# Microcontroller_Schematic.net
KiCad netlist of a schematic drawn in Altium Designer
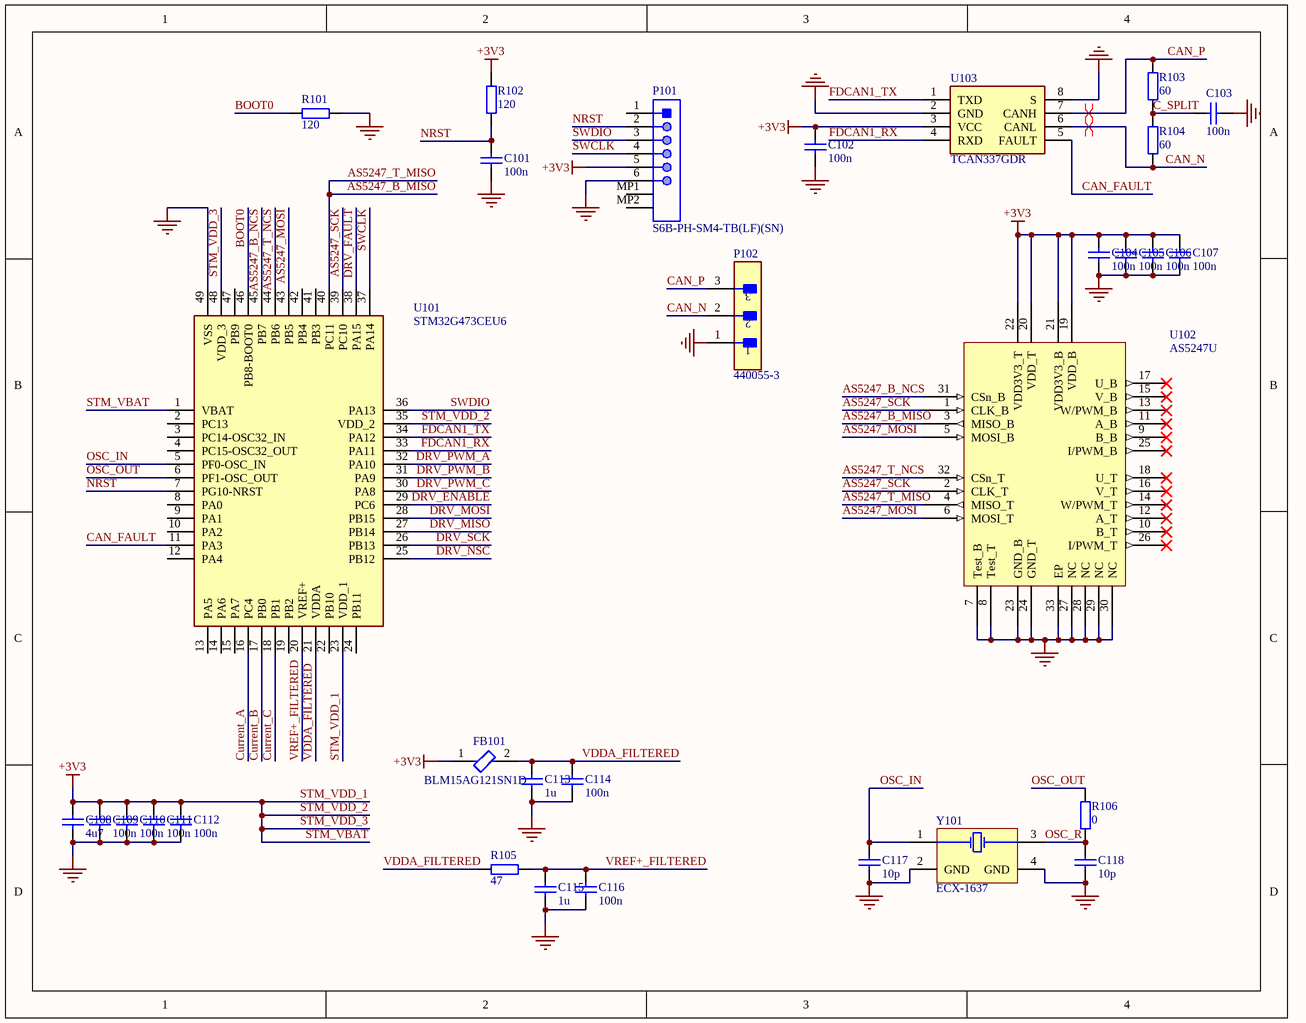
[diagram p0: Microcontroller Schematic.SchDoc]

(export (version "E")
  (design (tool "Eeschema 10.0.6"))
  (components
    (comp (ref "C101")
      (value "100n")
      (footprint "FootprintLib:CAPC1005X55N")
      (description "Capacitor")
      (fields
        (field (name "MANUFACTURER_PART_NUMBER") "CL05B104KO5NNNC")
        (field (name "MOUSER PART NUMBER") "187-CL05B104KO5NNNC")
      )
      (libsource (lib "SymbolLib") (part "CAP_0402_16V"))
    )
    (comp (ref "C102")
      (value "100n")
      (footprint "FootprintLib:CAPC1005X55N")
      (description "Capacitor")
      (fields
        (field (name "MANUFACTURER_PART_NUMBER") "CL05B104KO5NNNC")
        (field (name "MOUSER PART NUMBER") "187-CL05B104KO5NNNC")
      )
      (libsource (lib "SymbolLib") (part "CAP_0402_16V"))
    )
    (comp (ref "C103")
      (value "100n")
      (footprint "FootprintLib:CAPC1005X55N")
      (description "Capacitor")
      (fields
        (field (name "MANUFACTURER_PART_NUMBER") "CL05B104KO5NNNC")
        (field (name "MOUSER PART NUMBER") "187-CL05B104KO5NNNC")
      )
      (libsource (lib "SymbolLib") (part "CAP_0402_16V"))
    )
    (comp (ref "C104")
      (value "100n")
      (footprint "FootprintLib:CAPC1005X55N")
      (description "Capacitor")
      (fields
        (field (name "MANUFACTURER_PART_NUMBER") "CL05B104KO5NNNC")
        (field (name "MOUSER PART NUMBER") "187-CL05B104KO5NNNC")
      )
      (libsource (lib "SymbolLib") (part "CAP_0402_16V"))
    )
    (comp (ref "C105")
      (value "100n")
      (footprint "FootprintLib:CAPC1005X55N")
      (description "Capacitor")
      (fields
        (field (name "MANUFACTURER_PART_NUMBER") "CL05B104KO5NNNC")
        (field (name "MOUSER PART NUMBER") "187-CL05B104KO5NNNC")
      )
      (libsource (lib "SymbolLib") (part "CAP_0402_16V"))
    )
    (comp (ref "C106")
      (value "100n")
      (footprint "FootprintLib:CAPC1005X55N")
      (description "Capacitor")
      (fields
        (field (name "MANUFACTURER_PART_NUMBER") "CL05B104KO5NNNC")
        (field (name "MOUSER PART NUMBER") "187-CL05B104KO5NNNC")
      )
      (libsource (lib "SymbolLib") (part "CAP_0402_16V"))
    )
    (comp (ref "C107")
      (value "100n")
      (footprint "FootprintLib:CAPC1005X55N")
      (description "Capacitor")
      (fields
        (field (name "MANUFACTURER_PART_NUMBER") "CL05B104KO5NNNC")
        (field (name "MOUSER PART NUMBER") "187-CL05B104KO5NNNC")
      )
      (libsource (lib "SymbolLib") (part "CAP_0402_16V"))
    )
    (comp (ref "C108")
      (value "4u7")
      (footprint "FootprintLib:CAPC1608X90N")
      (description "Capacitor")
      (fields
        (field (name "MANUFACTURER_PART_NUMBER") "CL05B104KO5NNNC")
        (field (name "MOUSER PART NUMBER") "187-CL05B104KO5NNNC")
      )
      (libsource (lib "SymbolLib") (part "CAP_0603_16V"))
    )
    (comp (ref "C109")
      (value "100n")
      (footprint "FootprintLib:CAPC1005X55N")
      (description "Capacitor")
      (fields
        (field (name "MANUFACTURER_PART_NUMBER") "CL05B104KO5NNNC")
        (field (name "MOUSER PART NUMBER") "187-CL05B104KO5NNNC")
      )
      (libsource (lib "SymbolLib") (part "CAP_0402_16V"))
    )
    (comp (ref "C110")
      (value "100n")
      (footprint "FootprintLib:CAPC1005X55N")
      (description "Capacitor")
      (fields
        (field (name "MANUFACTURER_PART_NUMBER") "CL05B104KO5NNNC")
        (field (name "MOUSER PART NUMBER") "187-CL05B104KO5NNNC")
      )
      (libsource (lib "SymbolLib") (part "CAP_0402_16V"))
    )
    (comp (ref "C111")
      (value "100n")
      (footprint "FootprintLib:CAPC1005X55N")
      (description "Capacitor")
      (fields
        (field (name "MANUFACTURER_PART_NUMBER") "CL05B104KO5NNNC")
        (field (name "MOUSER PART NUMBER") "187-CL05B104KO5NNNC")
      )
      (libsource (lib "SymbolLib") (part "CAP_0402_16V"))
    )
    (comp (ref "C112")
      (value "100n")
      (footprint "FootprintLib:CAPC1005X55N")
      (description "Capacitor")
      (fields
        (field (name "MANUFACTURER_PART_NUMBER") "CL05B104KO5NNNC")
        (field (name "MOUSER PART NUMBER") "187-CL05B104KO5NNNC")
      )
      (libsource (lib "SymbolLib") (part "CAP_0402_16V"))
    )
    (comp (ref "C113")
      (value "1u")
      (footprint "FootprintLib:CAPC1005X55N")
      (description "Capacitor")
      (fields
        (field (name "MANUFACTURER_PART_NUMBER") "CL05B104KO5NNNC")
        (field (name "MOUSER PART NUMBER") "187-CL05B104KO5NNNC")
      )
      (libsource (lib "SymbolLib") (part "CAP_0402_16V"))
    )
    (comp (ref "C114")
      (value "100n")
      (footprint "FootprintLib:CAPC1005X55N")
      (description "Capacitor")
      (fields
        (field (name "MANUFACTURER_PART_NUMBER") "CL05B104KO5NNNC")
        (field (name "MOUSER PART NUMBER") "187-CL05B104KO5NNNC")
      )
      (libsource (lib "SymbolLib") (part "CAP_0402_16V"))
    )
    (comp (ref "C115")
      (value "1u")
      (footprint "FootprintLib:CAPC1005X55N")
      (description "Capacitor")
      (fields
        (field (name "MANUFACTURER_PART_NUMBER") "CL05B104KO5NNNC")
        (field (name "MOUSER PART NUMBER") "187-CL05B104KO5NNNC")
      )
      (libsource (lib "SymbolLib") (part "CAP_0402_16V"))
    )
    (comp (ref "C116")
      (value "100n")
      (footprint "FootprintLib:CAPC1005X55N")
      (description "Capacitor")
      (fields
        (field (name "MANUFACTURER_PART_NUMBER") "CL05B104KO5NNNC")
        (field (name "MOUSER PART NUMBER") "187-CL05B104KO5NNNC")
      )
      (libsource (lib "SymbolLib") (part "CAP_0402_16V"))
    )
    (comp (ref "C117")
      (value "10p")
      (footprint "FootprintLib:CAPC1005X55N")
      (description "Capacitor")
      (fields
        (field (name "MANUFACTURER_PART_NUMBER") "CL05B104KO5NNNC")
        (field (name "MOUSER PART NUMBER") "187-CL05B104KO5NNNC")
      )
      (libsource (lib "SymbolLib") (part "CAP_0402_16V"))
    )
    (comp (ref "C118")
      (value "10p")
      (footprint "FootprintLib:CAPC1005X55N")
      (description "Capacitor")
      (fields
        (field (name "MANUFACTURER_PART_NUMBER") "CL05B104KO5NNNC")
        (field (name "MOUSER PART NUMBER") "187-CL05B104KO5NNNC")
      )
      (libsource (lib "SymbolLib") (part "CAP_0402_16V"))
    )
    (comp (ref "FB101")
      (value "BLM15AG121SN1D")
      (footprint "FP-BLM15-0_05-MFG")
      (description "Chip Ferrite Bead, 0402, 120Ω @ 100MHz, 0.19Ω, 25%, 550mA")
      (fields (field (name "TOLERANCE") "25%"))
      (libsource (lib "Altium Content Vault") (part "5f30dd21d616792df468990f7003faa"))
    )
    (comp (ref "P101")
      (value "S6B-PH-SM4-TB(LF)(SN)")
      (footprint "JST-S6B-PH-SM4-TB(LF)(SN)_V")
      (description "Male Header, Pitch 2 mm, 1 x 6 Position, Height 5.5 mm, -25 to 85 degC")
      (fields (field (name "MANUFACTURER") "JST"))
      (libsource (lib "Altium Content Vault") (part "CN-1P-2M-R6"))
    )
    (comp (ref "P102")
      (value "440055-3")
      (footprint "FP-440055-3-MFG")
      (description "CONN HEADER R/A 3POS 2MM")
      (fields
        (field (name "MANUFACTURER") "TE Connectivity")
        (field (name "OCTOPART") "https://octopart.com/440055-3-te+connectivity-40644627")
      )
      (libsource (lib "Altium Content Vault") (part "0d3f023dd272f625e17a2be33dea85f"))
    )
    (comp (ref "R101")
      (value "120")
      (footprint "FootprintLib:RESC1005X40N")
      (libsource (lib "SymbolLib") (part "RES_0402"))
    )
    (comp (ref "R102")
      (value "120")
      (footprint "FootprintLib:RESC1005X40N")
      (libsource (lib "SymbolLib") (part "RES_0402"))
    )
    (comp (ref "R103")
      (value "60")
      (footprint "FootprintLib:RESC1005X40N")
      (libsource (lib "SymbolLib") (part "RES_0402"))
    )
    (comp (ref "R104")
      (value "60")
      (footprint "FootprintLib:RESC1005X40N")
      (libsource (lib "SymbolLib") (part "RES_0402"))
    )
    (comp (ref "R105")
      (value "47")
      (footprint "FootprintLib:RESC1005X40N")
      (libsource (lib "SymbolLib") (part "RES_0402"))
    )
    (comp (ref "R106")
      (value "0")
      (footprint "FootprintLib:RESC1005X40N")
      (libsource (lib "SymbolLib") (part "RES_0402"))
    )
    (comp (ref "U101")
      (value "STM32G473CEU6")
      (footprint "SamacSys:QFN50P700X700X65-49N-D")
      (description "Integrated Circuit")
      (fields (field (name "MOUSER PART NUMBER") "511-STM32G473CEU6"))
      (libsource (lib "*") (part "STM32G473CEU6"))
    )
    (comp (ref "U102")
      (value "AS5247U")
      (footprint "QFN-N32-THM")
      (description "ams AS5247U Magnetic Rotary Position Sensor")
      (libsource (lib "SymbolLib") (part "AS5247U"))
    )
    (comp (ref "U103")
      (value "TCAN337GDR")
      (footprint "SamacSys:SOIC127P600X175-8N")
      (description "Integrated Circuit")
      (fields (field (name "MOUSER PART NUMBER") "595-TCAN337GDR"))
      (libsource (lib "*") (part "TCAN337GDR"))
    )
    (comp (ref "Y101")
      (value "ECX-1637")
      (footprint "ECX-1637")
      (libsource (lib "SymbolLib") (part "ECX-1637"))
    )
  )
  (nets
    (net (code "1") (name "+3V3") (class "Default")
      (node (ref "C102") (pin "2") (pinfunction "2_2") (pintype "passive"))
      (node (ref "C104") (pin "2") (pinfunction "2_2") (pintype "passive"))
      (node (ref "C105") (pin "2") (pinfunction "2_2") (pintype "passive"))
      (node (ref "C106") (pin "2") (pinfunction "2_2") (pintype "passive"))
      (node (ref "C107") (pin "2") (pinfunction "2_2") (pintype "passive"))
      (node (ref "C108") (pin "1") (pinfunction "1_1") (pintype "passive"))
      (node (ref "C109") (pin "2") (pinfunction "2_2") (pintype "passive"))
      (node (ref "C110") (pin "2") (pinfunction "2_2") (pintype "passive"))
      (node (ref "C111") (pin "2") (pinfunction "2_2") (pintype "passive"))
      (node (ref "C112") (pin "2") (pinfunction "2_2") (pintype "passive"))
      (node (ref "FB101") (pin "1") (pinfunction "1_1") (pintype "passive"))
      (node (ref "P101") (pin "5") (pinfunction "5_5") (pintype "passive"))
      (node (ref "R102") (pin "1") (pinfunction "1_1") (pintype "passive"))
      (node (ref "U101") (pin "1") (pinfunction "VBAT_1") (pintype "passive"))
      (node (ref "U101") (pin "23") (pinfunction "VDD_1_23") (pintype "passive"))
      (node (ref "U101") (pin "35") (pinfunction "VDD_2_35") (pintype "passive"))
      (node (ref "U101") (pin "48") (pinfunction "VDD_3_48") (pintype "passive"))
      (node (ref "U102") (pin "19") (pinfunction "VDD_B_19") (pintype "power_in"))
      (node (ref "U102") (pin "20") (pinfunction "VDD_T_20") (pintype "power_in"))
      (node (ref "U102") (pin "21") (pinfunction "VDD3V3_B_21") (pintype "power_in"))
      (node (ref "U102") (pin "22") (pinfunction "VDD3V3_T_22") (pintype "power_in"))
      (node (ref "U103") (pin "3") (pinfunction "VCC_3") (pintype "passive"))
    )
    (net (code "2") (name "/AS5247_B_MISO") (class "Default")
      (node (ref "U101") (pin "40") (pinfunction "PC11_40") (pintype "passive"))
      (node (ref "U102") (pin "3") (pinfunction "MISO_B_3") (pintype "output"))
      (node (ref "U102") (pin "4") (pinfunction "MISO_T_4") (pintype "output"))
    )
    (net (code "3") (name "/AS5247_B_NCS") (class "Default")
      (node (ref "U101") (pin "45") (pinfunction "PB7_45") (pintype "passive"))
      (node (ref "U102") (pin "31") (pinfunction "CSn_B_31") (pintype "input"))
    )
    (net (code "4") (name "/AS5247_MOSI") (class "Default")
      (node (ref "U101") (pin "43") (pinfunction "PB5_43") (pintype "passive"))
      (node (ref "U102") (pin "5") (pinfunction "MOSI_B_5") (pintype "input"))
      (node (ref "U102") (pin "6") (pinfunction "MOSI_T_6") (pintype "input"))
    )
    (net (code "5") (name "/AS5247_SCK") (class "Default")
      (node (ref "U101") (pin "39") (pinfunction "PC10_39") (pintype "passive"))
      (node (ref "U102") (pin "1") (pinfunction "CLK_B_1") (pintype "input"))
      (node (ref "U102") (pin "2") (pinfunction "CLK_T_2") (pintype "input"))
    )
    (net (code "6") (name "/AS5247_T_NCS") (class "Default")
      (node (ref "U101") (pin "44") (pinfunction "PB6_44") (pintype "passive"))
      (node (ref "U102") (pin "32") (pinfunction "CSn_T_32") (pintype "input"))
    )
    (net (code "7") (name "/BOOT0") (class "Default")
      (node (ref "R101") (pin "1") (pinfunction "1_1") (pintype "passive"))
      (node (ref "U101") (pin "46") (pinfunction "PB8-BOOT0_46") (pintype "passive"))
    )
    (net (code "8") (name "/CAN_FAULT") (class "Default")
      (node (ref "U101") (pin "11") (pinfunction "PA3_11") (pintype "passive"))
      (node (ref "U103") (pin "5") (pinfunction "FAULT_5") (pintype "passive"))
    )
    (net (code "9") (name "/CAN_N") (class "Default")
      (node (ref "P102") (pin "2") (pinfunction "2_2") (pintype "passive"))
      (node (ref "R104") (pin "1") (pinfunction "1_1") (pintype "passive"))
      (node (ref "U103") (pin "6") (pinfunction "CANL_6") (pintype "passive"))
    )
    (net (code "10") (name "/CAN_P") (class "Default")
      (node (ref "P102") (pin "3") (pinfunction "3_3") (pintype "passive"))
      (node (ref "R103") (pin "2") (pinfunction "2_2") (pintype "passive"))
      (node (ref "U103") (pin "7") (pinfunction "CANH_7") (pintype "passive"))
    )
    (net (code "11") (name "/C_SPLIT") (class "Default")
      (node (ref "C103") (pin "1") (pinfunction "1_1") (pintype "passive"))
      (node (ref "R103") (pin "1") (pinfunction "1_1") (pintype "passive"))
      (node (ref "R104") (pin "2") (pinfunction "2_2") (pintype "passive"))
    )
    (net (code "12") (name "/Current_A") (class "Default")
      (node (ref "U101") (pin "16") (pinfunction "PC4_16") (pintype "passive"))
    )
    (net (code "13") (name "/Current_B") (class "Default")
      (node (ref "U101") (pin "17") (pinfunction "PB0_17") (pintype "passive"))
    )
    (net (code "14") (name "/Current_C") (class "Default")
      (node (ref "U101") (pin "18") (pinfunction "PB1_18") (pintype "passive"))
    )
    (net (code "15") (name "/DRV_ENABLE") (class "Default")
      (node (ref "U101") (pin "29") (pinfunction "PC6_29") (pintype "passive"))
    )
    (net (code "16") (name "/DRV_FAULT") (class "Default")
      (node (ref "U101") (pin "38") (pinfunction "PA15_38") (pintype "passive"))
    )
    (net (code "17") (name "/DRV_MISO") (class "Default")
      (node (ref "U101") (pin "27") (pinfunction "PB14_27") (pintype "passive"))
    )
    (net (code "18") (name "/DRV_MOSI") (class "Default")
      (node (ref "U101") (pin "28") (pinfunction "PB15_28") (pintype "passive"))
    )
    (net (code "19") (name "/DRV_NSC") (class "Default")
      (node (ref "U101") (pin "25") (pinfunction "PB12_25") (pintype "passive"))
    )
    (net (code "20") (name "/DRV_PWM_A") (class "Default")
      (node (ref "U101") (pin "32") (pinfunction "PA10_32") (pintype "passive"))
    )
    (net (code "21") (name "/DRV_PWM_B") (class "Default")
      (node (ref "U101") (pin "31") (pinfunction "PA9_31") (pintype "passive"))
    )
    (net (code "22") (name "/DRV_PWM_C") (class "Default")
      (node (ref "U101") (pin "30") (pinfunction "PA8_30") (pintype "passive"))
    )
    (net (code "23") (name "/DRV_SCK") (class "Default")
      (node (ref "U101") (pin "26") (pinfunction "PB13_26") (pintype "passive"))
    )
    (net (code "24") (name "/FDCAN1_RX") (class "Default")
      (node (ref "U101") (pin "33") (pinfunction "PA11_33") (pintype "passive"))
      (node (ref "U103") (pin "4") (pinfunction "RXD_4") (pintype "passive"))
    )
    (net (code "25") (name "/FDCAN1_TX") (class "Default")
      (node (ref "U101") (pin "34") (pinfunction "PA12_34") (pintype "passive"))
      (node (ref "U103") (pin "1") (pinfunction "TXD_1") (pintype "passive"))
    )
    (net (code "26") (name "/NRST") (class "Default")
      (node (ref "C101") (pin "1") (pinfunction "1_1") (pintype "passive"))
      (node (ref "P101") (pin "2") (pinfunction "2_2") (pintype "passive"))
      (node (ref "R102") (pin "2") (pinfunction "2_2") (pintype "passive"))
      (node (ref "U101") (pin "7") (pinfunction "PG10-NRST_7") (pintype "passive"))
    )
    (net (code "27") (name "/OSC_IN") (class "Default")
      (node (ref "C117") (pin "2") (pinfunction "2_2") (pintype "passive"))
      (node (ref "U101") (pin "5") (pinfunction "PF0-OSC_IN_5") (pintype "passive"))
      (node (ref "Y101") (pin "1") (pinfunction "X1_1") (pintype "passive"))
    )
    (net (code "28") (name "/OSC_OUT") (class "Default")
      (node (ref "R106") (pin "1") (pinfunction "1_1") (pintype "passive"))
      (node (ref "U101") (pin "6") (pinfunction "PF1-OSC_OUT_6") (pintype "passive"))
    )
    (net (code "29") (name "/OSC_R") (class "Default")
      (node (ref "C118") (pin "2") (pinfunction "2_2") (pintype "passive"))
      (node (ref "R106") (pin "2") (pinfunction "2_2") (pintype "passive"))
      (node (ref "Y101") (pin "3") (pinfunction "X2_3") (pintype "passive"))
    )
    (net (code "30") (name "/SWCLK") (class "Default")
      (node (ref "P101") (pin "4") (pinfunction "4_4") (pintype "passive"))
      (node (ref "U101") (pin "37") (pinfunction "PA14_37") (pintype "passive"))
    )
    (net (code "31") (name "/SWDIO") (class "Default")
      (node (ref "P101") (pin "3") (pinfunction "3_3") (pintype "passive"))
      (node (ref "U101") (pin "36") (pinfunction "PA13_36") (pintype "passive"))
    )
    (net (code "32") (name "/VDDA_FILTERED") (class "Default")
      (node (ref "C113") (pin "2") (pinfunction "2_2") (pintype "passive"))
      (node (ref "C114") (pin "2") (pinfunction "2_2") (pintype "passive"))
      (node (ref "FB101") (pin "2") (pinfunction "2_2") (pintype "passive"))
      (node (ref "R105") (pin "1") (pinfunction "1_1") (pintype "passive"))
      (node (ref "U101") (pin "21") (pinfunction "VDDA_21") (pintype "passive"))
    )
    (net (code "33") (name "/VREF+_FILTERED") (class "Default")
      (node (ref "C115") (pin "2") (pinfunction "2_2") (pintype "passive"))
      (node (ref "C116") (pin "2") (pinfunction "2_2") (pintype "passive"))
      (node (ref "R105") (pin "2") (pinfunction "2_2") (pintype "passive"))
      (node (ref "U101") (pin "20") (pinfunction "VREF+_20") (pintype "passive"))
    )
    (net (code "34") (name "GND") (class "Default")
      (node (ref "C101") (pin "2") (pinfunction "2_2") (pintype "passive"))
      (node (ref "C102") (pin "1") (pinfunction "1_1") (pintype "passive"))
      (node (ref "C103") (pin "2") (pinfunction "2_2") (pintype "passive"))
      (node (ref "C104") (pin "1") (pinfunction "1_1") (pintype "passive"))
      (node (ref "C105") (pin "1") (pinfunction "1_1") (pintype "passive"))
      (node (ref "C106") (pin "1") (pinfunction "1_1") (pintype "passive"))
      (node (ref "C107") (pin "1") (pinfunction "1_1") (pintype "passive"))
      (node (ref "C108") (pin "2") (pinfunction "2_2") (pintype "passive"))
      (node (ref "C109") (pin "1") (pinfunction "1_1") (pintype "passive"))
      (node (ref "C110") (pin "1") (pinfunction "1_1") (pintype "passive"))
      (node (ref "C111") (pin "1") (pinfunction "1_1") (pintype "passive"))
      (node (ref "C112") (pin "1") (pinfunction "1_1") (pintype "passive"))
      (node (ref "C113") (pin "1") (pinfunction "1_1") (pintype "passive"))
      (node (ref "C114") (pin "1") (pinfunction "1_1") (pintype "passive"))
      (node (ref "C115") (pin "1") (pinfunction "1_1") (pintype "passive"))
      (node (ref "C116") (pin "1") (pinfunction "1_1") (pintype "passive"))
      (node (ref "C117") (pin "1") (pinfunction "1_1") (pintype "passive"))
      (node (ref "C118") (pin "1") (pinfunction "1_1") (pintype "passive"))
      (node (ref "P101") (pin "6") (pinfunction "6_6") (pintype "passive"))
      (node (ref "P102") (pin "1") (pinfunction "1_1") (pintype "passive"))
      (node (ref "R101") (pin "2") (pinfunction "2_2") (pintype "passive"))
      (node (ref "U101") (pin "49") (pinfunction "VSS_49") (pintype "passive"))
      (node (ref "U102") (pin "23") (pinfunction "GND_B_23") (pintype "power_in"))
      (node (ref "U102") (pin "24") (pinfunction "GND_T_24") (pintype "power_in"))
      (node (ref "U102") (pin "27") (pinfunction "NC_27") (pintype "passive"))
      (node (ref "U102") (pin "28") (pinfunction "NC_28") (pintype "passive"))
      (node (ref "U102") (pin "29") (pinfunction "NC_29") (pintype "passive"))
      (node (ref "U102") (pin "30") (pinfunction "NC_30") (pintype "passive"))
      (node (ref "U102") (pin "33") (pinfunction "EP_33") (pintype "passive"))
      (node (ref "U102") (pin "7") (pinfunction "Test_B_7") (pintype "power_in"))
      (node (ref "U102") (pin "8") (pinfunction "Test_T_8") (pintype "power_in"))
      (node (ref "U103") (pin "2") (pinfunction "GND_2") (pintype "passive"))
      (node (ref "U103") (pin "8") (pinfunction "S_8") (pintype "passive"))
      (node (ref "Y101") (pin "2") (pinfunction "GND_2") (pintype "power_in"))
      (node (ref "Y101") (pin "4") (pinfunction "GND_4") (pintype "power_in"))
    )
    (net (code "35") (name "unconnected-(P101-Pad1)") (class "Default")
      (node (ref "P101") (pin "1") (pinfunction "1_1") (pintype "passive"))
    )
    (net (code "36") (name "unconnected-(P101-PadMP1)") (class "Default")
      (node (ref "P101") (pin "MP1") (pinfunction "MP1_MP1") (pintype "passive"))
    )
    (net (code "37") (name "unconnected-(P101-PadMP2)") (class "Default")
      (node (ref "P101") (pin "MP2") (pinfunction "MP2_MP2") (pintype "passive"))
    )
    (net (code "38") (name "unconnected-(U101-PA0-Pad8)") (class "Default")
      (node (ref "U101") (pin "8") (pinfunction "PA0_8") (pintype "passive"))
    )
    (net (code "39") (name "unconnected-(U101-PA1-Pad9)") (class "Default")
      (node (ref "U101") (pin "9") (pinfunction "PA1_9") (pintype "passive"))
    )
    (net (code "40") (name "unconnected-(U101-PA2-Pad10)") (class "Default")
      (node (ref "U101") (pin "10") (pinfunction "PA2_10") (pintype "passive"))
    )
    (net (code "41") (name "unconnected-(U101-PA4-Pad12)") (class "Default")
      (node (ref "U101") (pin "12") (pinfunction "PA4_12") (pintype "passive"))
    )
    (net (code "42") (name "unconnected-(U101-PA5-Pad13)") (class "Default")
      (node (ref "U101") (pin "13") (pinfunction "PA5_13") (pintype "passive"))
    )
    (net (code "43") (name "unconnected-(U101-PA6-Pad14)") (class "Default")
      (node (ref "U101") (pin "14") (pinfunction "PA6_14") (pintype "passive"))
    )
    (net (code "44") (name "unconnected-(U101-PA7-Pad15)") (class "Default")
      (node (ref "U101") (pin "15") (pinfunction "PA7_15") (pintype "passive"))
    )
    (net (code "45") (name "unconnected-(U101-PB2-Pad19)") (class "Default")
      (node (ref "U101") (pin "19") (pinfunction "PB2_19") (pintype "passive"))
    )
    (net (code "46") (name "unconnected-(U101-PB3-Pad41)") (class "Default")
      (node (ref "U101") (pin "41") (pinfunction "PB3_41") (pintype "passive"))
    )
    (net (code "47") (name "unconnected-(U101-PB4-Pad42)") (class "Default")
      (node (ref "U101") (pin "42") (pinfunction "PB4_42") (pintype "passive"))
    )
    (net (code "48") (name "unconnected-(U101-PB9-Pad47)") (class "Default")
      (node (ref "U101") (pin "47") (pinfunction "PB9_47") (pintype "passive"))
    )
    (net (code "49") (name "unconnected-(U101-PB10-Pad22)") (class "Default")
      (node (ref "U101") (pin "22") (pinfunction "PB10_22") (pintype "passive"))
    )
    (net (code "50") (name "unconnected-(U101-PB11-Pad24)") (class "Default")
      (node (ref "U101") (pin "24") (pinfunction "PB11_24") (pintype "passive"))
    )
    (net (code "51") (name "unconnected-(U101-PC13-Pad2)") (class "Default")
      (node (ref "U101") (pin "2") (pinfunction "PC13_2") (pintype "passive"))
    )
    (net (code "52") (name "unconnected-(U101-PC14-OSC32_IN-Pad3)") (class "Default")
      (node (ref "U101") (pin "3") (pinfunction "PC14-OSC32_IN_3") (pintype "passive"))
    )
    (net (code "53") (name "unconnected-(U101-PC15-OSC32_OUT-Pad4)") (class "Default")
      (node (ref "U101") (pin "4") (pinfunction "PC15-OSC32_OUT_4") (pintype "passive"))
    )
    (net (code "54") (name "unconnected-(U102-A_B-Pad11)") (class "Default")
      (node (ref "U102") (pin "11") (pinfunction "A_B_11") (pintype "output+no_connect"))
    )
    (net (code "55") (name "unconnected-(U102-A_T-Pad12)") (class "Default")
      (node (ref "U102") (pin "12") (pinfunction "A_T_12") (pintype "output+no_connect"))
    )
    (net (code "56") (name "unconnected-(U102-B_B-Pad9)") (class "Default")
      (node (ref "U102") (pin "9") (pinfunction "B_B_9") (pintype "output+no_connect"))
    )
    (net (code "57") (name "unconnected-(U102-B_T-Pad10)") (class "Default")
      (node (ref "U102") (pin "10") (pinfunction "B_T_10") (pintype "output+no_connect"))
    )
    (net (code "58") (name "unconnected-(U102-I{slash}PWM_B-Pad25)") (class "Default")
      (node (ref "U102") (pin "25") (pinfunction "I/PWM_B_25") (pintype "output+no_connect"))
    )
    (net (code "59") (name "unconnected-(U102-I{slash}PWM_T-Pad26)") (class "Default")
      (node (ref "U102") (pin "26") (pinfunction "I/PWM_T_26") (pintype "output+no_connect"))
    )
    (net (code "60") (name "unconnected-(U102-U_B-Pad17)") (class "Default")
      (node (ref "U102") (pin "17") (pinfunction "U_B_17") (pintype "output+no_connect"))
    )
    (net (code "61") (name "unconnected-(U102-U_T-Pad18)") (class "Default")
      (node (ref "U102") (pin "18") (pinfunction "U_T_18") (pintype "output+no_connect"))
    )
    (net (code "62") (name "unconnected-(U102-V_B-Pad15)") (class "Default")
      (node (ref "U102") (pin "15") (pinfunction "V_B_15") (pintype "output+no_connect"))
    )
    (net (code "63") (name "unconnected-(U102-V_T-Pad16)") (class "Default")
      (node (ref "U102") (pin "16") (pinfunction "V_T_16") (pintype "output+no_connect"))
    )
    (net (code "64") (name "unconnected-(U102-W{slash}PWM_B-Pad13)") (class "Default")
      (node (ref "U102") (pin "13") (pinfunction "W/PWM_B_13") (pintype "output+no_connect"))
    )
    (net (code "65") (name "unconnected-(U102-W{slash}PWM_T-Pad14)") (class "Default")
      (node (ref "U102") (pin "14") (pinfunction "W/PWM_T_14") (pintype "output+no_connect"))
    )
  )
)
